# USB_and_CAN_Page_6.net
KiCad netlist of a schematic drawn in Altium Designer
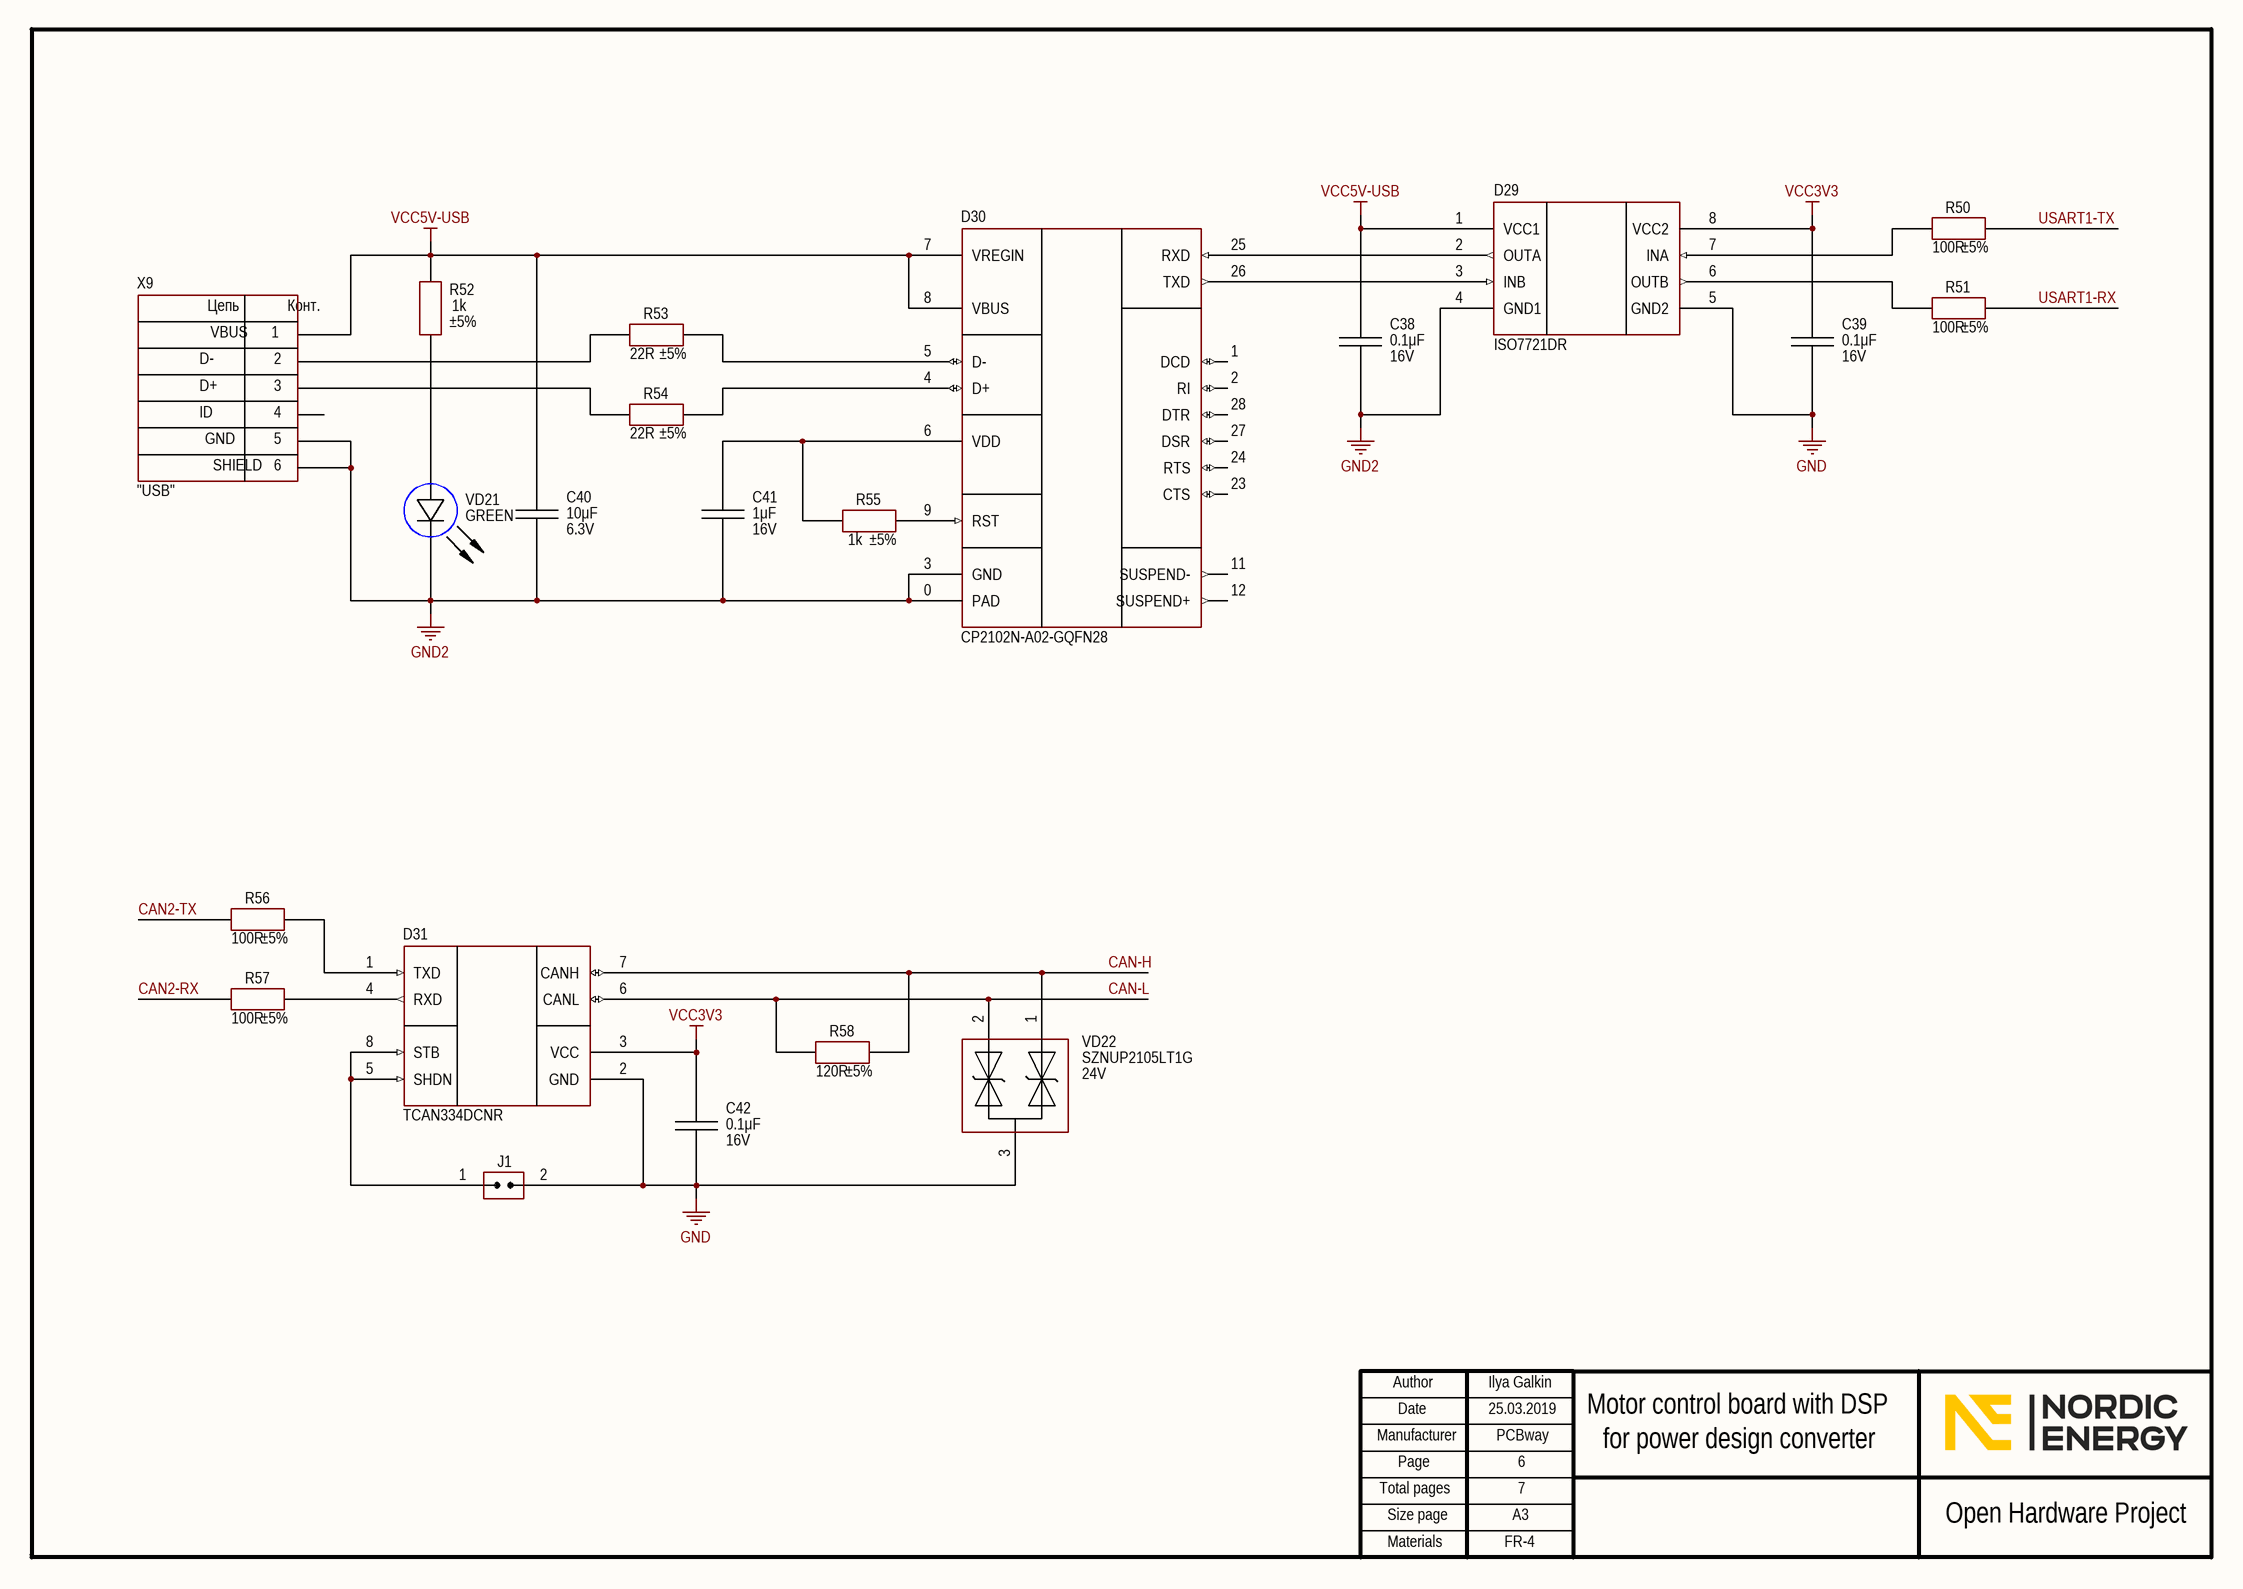
[diagram p0: USB and CAN. Page 6.SchDoc]

(export (version "E")
  (design (tool "Eeschema 10.0.6"))
  (components
    (comp (ref "C38")
      (value "0.1μF")
      (footprint "CAP: 0805")
      (fields
        (field (name "MANUFACTURER") "Yageo")
        (field (name "PARTNUMBER") "CC0805KRX7R7BB104")
        (field (name "VALUEMANUFACTURERPARTNUMBER") "Ceramic capacitor, 0.1μF, X7R, ±10%, 16V, 0805, -55...+125°C")
        (field (name "VOLTAGE") "16V")
      )
      (libsource (lib "Capacitor") (part "Ceramic_0805"))
    )
    (comp (ref "C39")
      (value "0.1μF")
      (footprint "CAP: 0805")
      (fields
        (field (name "MANUFACTURER") "Yageo")
        (field (name "PARTNUMBER") "CC0805KRX7R7BB104")
        (field (name "VALUEMANUFACTURERPARTNUMBER") "Ceramic capacitor, 0.1μF, X7R, ±10%, 16V, 0805, -55...+125°C")
        (field (name "VOLTAGE") "16V")
      )
      (libsource (lib "Capacitor") (part "Ceramic_0805"))
    )
    (comp (ref "C40")
      (value "10μF")
      (footprint "CAP: 0805")
      (fields
        (field (name "MANUFACTURER") "Samsung")
        (field (name "PARTNUMBER") "CL21B106KQQNNNE")
        (field (name "VALUEMANUFACTURERPARTNUMBER") "Ceramic capacitor, 10μF, X7R, ±10%, 6.3V, 0805, -55...+125°C")
        (field (name "VOLTAGE") "6.3V")
      )
      (libsource (lib "Capacitor") (part "Ceramic_0805"))
    )
    (comp (ref "C41")
      (value "1μF")
      (footprint "CAP: 0805")
      (fields
        (field (name "MANUFACTURER") "Yageo")
        (field (name "PARTNUMBER") "CC0805KKX7R7BB105")
        (field (name "VALUEMANUFACTURERPARTNUMBER") "Ceramic capacitor, 1μF, X7R, ±10%, 16V, 0805, -55...+125°C")
        (field (name "VOLTAGE") "16V")
      )
      (libsource (lib "Capacitor") (part "Ceramic_0805"))
    )
    (comp (ref "C42")
      (value "0.1μF")
      (footprint "CAP: 0805")
      (fields
        (field (name "MANUFACTURER") "Yageo")
        (field (name "PARTNUMBER") "CC0805KRX7R7BB104")
        (field (name "VALUEMANUFACTURERPARTNUMBER") "Ceramic capacitor, 0.1μF, X7R, ±10%, 16V, 0805, -55...+125°C")
        (field (name "VOLTAGE") "16V")
      )
      (libsource (lib "Capacitor") (part "Ceramic_0805"))
    )
    (comp (ref "D29")
      (value "~")
      (footprint "8-SOIC")
      (description "Digital isolator")
      (fields
        (field (name "MANUFACTURER") "Texas Instruments")
        (field (name "VALUEMANUFACTURERPARTNUMBER") "IC digital isolator, 100Mbps, 3000Vrms, 2.25...5.5V, -55...+125°C, 8-SOIC")
        (field (name "PARTNUMBER") "ISO7721DR")
      )
      (libsource (lib "IC. Interface") (part "ISO7721DR"))
    )
    (comp (ref "D30")
      (value "~")
      (footprint "28-QFN (5x5)")
      (description "USB-to-UART")
      (fields
        (field (name "MANUFACTURER") "Silicon Labs")
        (field (name "VALUEMANUFACTURERPARTNUMBER") "IC usb-to-uart bridge, USB2.0, 3...3.6V, -40...+85°C, 28-VFQFN")
        (field (name "PARTNUMBER") "CP2102N-A02-GQFN28")
      )
      (libsource (lib "IC. Interface") (part "CP2102N"))
    )
    (comp (ref "D31")
      (value "~")
      (footprint "SOT23-8")
      (description "CAN")
      (fields
        (field (name "MANUFACTURER") "Texas Instruments")
        (field (name "VALUEMANUFACTURERPARTNUMBER") "IC CAN transceiver, 1Mbps, Half-duplex, 3...3.6V, -40...+125°C, SOT23-8")
        (field (name "PARTNUMBER") "TCAN334DCNR")
      )
      (libsource (lib "IC. Interface") (part "TCAN334DCNR"))
    )
    (comp (ref "J1")
      (value "~")
      (footprint "CON: JUMPER x1")
      (libsource (lib "Connector") (part "Jumper_single"))
    )
    (comp (ref "R50")
      (value "100R")
      (footprint "RES: 0805")
      (fields
        (field (name "MANUFACTURER") "Yageo")
        (field (name "PARTNUMBER") "RC0805JR-07100RL")
        (field (name "VALUEMANUFACTURERPARTNUMBER") "Resistor film, 100R, ±5%, 0805, 0.125W, -55...+125°C")
        (field (name "TOLERANCE") "±5%")
      )
      (libsource (lib "Resistor") (part "Resistor_0805"))
    )
    (comp (ref "R51")
      (value "100R")
      (footprint "RES: 0805")
      (fields
        (field (name "MANUFACTURER") "Yageo")
        (field (name "PARTNUMBER") "RC0805JR-07100RL")
        (field (name "VALUEMANUFACTURERPARTNUMBER") "Resistor film, 100R, ±5%, 0805, 0.125W, -55...+125°C")
        (field (name "TOLERANCE") "±5%")
      )
      (libsource (lib "Resistor") (part "Resistor_0805"))
    )
    (comp (ref "R52")
      (value "1k")
      (footprint "RES: 0805")
      (fields
        (field (name "MANUFACTURER") "Yageo")
        (field (name "PARTNUMBER") "RC0805JR-071KL")
        (field (name "VALUEMANUFACTURERPARTNUMBER") "Resistor film, 1k, ±5%, 0805, 0.125W, -55...+125°C")
        (field (name "TOLERANCE") "±5%")
      )
      (libsource (lib "") (part "Resistor_0805_2"))
    )
    (comp (ref "R53")
      (value "22R")
      (footprint "RES: 0805")
      (fields
        (field (name "MANUFACTURER") "Yageo")
        (field (name "PARTNUMBER") "RC0805JR-0722RL")
        (field (name "VALUEMANUFACTURERPARTNUMBER") "Resistor film, 22R, ±5%, 0805, 0.125W, -55...+125°C")
        (field (name "TOLERANCE") "±5%")
      )
      (libsource (lib "Resistor") (part "Resistor_0805"))
    )
    (comp (ref "R54")
      (value "22R")
      (footprint "RES: 0805")
      (fields
        (field (name "MANUFACTURER") "Yageo")
        (field (name "PARTNUMBER") "RC0805JR-0722RL")
        (field (name "VALUEMANUFACTURERPARTNUMBER") "Resistor film, 22R, ±5%, 0805, 0.125W, -55...+125°C")
        (field (name "TOLERANCE") "±5%")
      )
      (libsource (lib "Resistor") (part "Resistor_0805"))
    )
    (comp (ref "R55")
      (value "1k")
      (footprint "RES: 0805")
      (fields
        (field (name "MANUFACTURER") "Yageo")
        (field (name "PARTNUMBER") "RC0805JR-071KL")
        (field (name "VALUEMANUFACTURERPARTNUMBER") "Resistor film, 1k, ±5%, 0805, 0.125W, -55...+125°C")
        (field (name "TOLERANCE") "±5%")
      )
      (libsource (lib "") (part "Resistor_0805_1"))
    )
    (comp (ref "R56")
      (value "100R")
      (footprint "RES: 0805")
      (fields
        (field (name "MANUFACTURER") "Yageo")
        (field (name "PARTNUMBER") "RC0805JR-07100RL")
        (field (name "VALUEMANUFACTURERPARTNUMBER") "Resistor film, 100R, ±5%, 0805, 0.125W, -55...+125°C")
        (field (name "TOLERANCE") "±5%")
      )
      (libsource (lib "Resistor") (part "Resistor_0805"))
    )
    (comp (ref "R57")
      (value "100R")
      (footprint "RES: 0805")
      (fields
        (field (name "MANUFACTURER") "Yageo")
        (field (name "PARTNUMBER") "RC0805JR-07100RL")
        (field (name "VALUEMANUFACTURERPARTNUMBER") "Resistor film, 100R, ±5%, 0805, 0.125W, -55...+125°C")
        (field (name "TOLERANCE") "±5%")
      )
      (libsource (lib "Resistor") (part "Resistor_0805"))
    )
    (comp (ref "R58")
      (value "120R")
      (footprint "RES: 0805")
      (fields
        (field (name "MANUFACTURER") "Yageo")
        (field (name "PARTNUMBER") "RC0805JR-07120RL")
        (field (name "VALUEMANUFACTURERPARTNUMBER") "Resistor film, 120R, ±5%, 0805, 0.125W, -55...+125°C")
        (field (name "TOLERANCE") "±5%")
      )
      (libsource (lib "Resistor") (part "Resistor_0805"))
    )
    (comp (ref "VD21")
      (value "~")
      (footprint "LED: 0603G")
      (fields
        (field (name "MANUFACTURER") "Wurth")
        (field (name "VALUEMANUFACTURERPARTNUMBER") "LED, 20mA, 2V, 0805, -55...+150°C")
        (field (name "PARTNUMBER") "150080VS75000")
        (field (name "COLOR") "GREEN")
      )
      (libsource (lib "Diode") (part "LED_single"))
    )
    (comp (ref "VD22")
      (value "~")
      (footprint "SOT23")
      (fields
        (field (name "MANUFACTURER") "ON Semiconductor")
        (field (name "VALUEMANUFACTURERPARTNUMBER") "Zener diode, 24V, 350W peak, 30pF, 17Ohm, SOT-23, -55...+150°C")
        (field (name "VOLTAGE") "24V")
        (field (name "PARTNUMBER") "SZNUP2105LT1G")
      )
      (libsource (lib "Diode") (part "TVS_array"))
    )
    (comp (ref "X9")
      (value "~")
      (footprint "CON: USB micro-A (ZX62-B-5PA)")
      (fields
        (field (name "MANUFACTURER") "Hirose Electric")
        (field (name "VALUEMANUFACTURERPARTNUMBER") "USB micro B")
        (field (name "PARTNUMBER") "ZX62-B-5PA")
        (field (name "COMMENTTEXT") "\"USB\"")
      )
      (libsource (lib "Connector") (part "Connector_USB_micro_B"))
    )
  )
  (nets
    (net (code "1") (name "/CAN-H") (class "Default")
      (node (ref "D31") (pin "7") (pinfunction "CANH_7") (pintype "bidirectional"))
      (node (ref "R58") (pin "2") (pinfunction "2_2") (pintype "passive"))
      (node (ref "VD22") (pin "1") (pintype "passive"))
    )
    (net (code "2") (name "/CAN-L") (class "Default")
      (node (ref "D31") (pin "6") (pinfunction "CANL_6") (pintype "bidirectional"))
      (node (ref "R58") (pin "1") (pinfunction "1_1") (pintype "passive"))
      (node (ref "VD22") (pin "2") (pintype "passive"))
    )
    (net (code "3") (name "/CAN2-RX") (class "Default")
      (node (ref "R57") (pin "1") (pinfunction "1_1") (pintype "passive"))
    )
    (net (code "4") (name "/CAN2-TX") (class "Default")
      (node (ref "R56") (pin "1") (pinfunction "1_1") (pintype "passive"))
    )
    (net (code "5") (name "/USART1-RX") (class "Default")
      (node (ref "R51") (pin "2") (pinfunction "2_2") (pintype "passive"))
    )
    (net (code "6") (name "/USART1-TX") (class "Default")
      (node (ref "R50") (pin "2") (pinfunction "2_2") (pintype "passive"))
    )
    (net (code "7") (name "GND") (class "Default")
      (node (ref "C39") (pin "1") (pinfunction "1_1") (pintype "power_in"))
      (node (ref "C42") (pin "1") (pinfunction "1_1") (pintype "power_in"))
      (node (ref "D29") (pin "5") (pinfunction "GND2_5") (pintype "passive"))
      (node (ref "D31") (pin "2") (pinfunction "GND_2") (pintype "passive"))
      (node (ref "J1") (pin "2") (pinfunction "IN_2") (pintype "passive"))
      (node (ref "VD22") (pin "3") (pintype "passive"))
    )
    (net (code "8") (name "GND2") (class "Default")
      (node (ref "C38") (pin "1") (pinfunction "1_1") (pintype "power_in"))
      (node (ref "C40") (pin "1") (pinfunction "1_1") (pintype "power_in"))
      (node (ref "C41") (pin "1") (pinfunction "1_1") (pintype "power_in"))
      (node (ref "D29") (pin "4") (pinfunction "GND1_4") (pintype "passive"))
      (node (ref "D30") (pin "0") (pinfunction "PAD_0") (pintype "passive"))
      (node (ref "D30") (pin "3") (pinfunction "GND_3") (pintype "passive"))
      (node (ref "VD21") (pin "2") (pinfunction "C_2") (pintype "passive"))
      (node (ref "X9") (pin "0") (pinfunction "0_0") (pintype "passive"))
      (node (ref "X9") (pin "5") (pinfunction "5_5") (pintype "passive"))
    )
    (net (code "9") (name "Net-(D29-INA)") (class "Default")
      (node (ref "D29") (pin "7") (pinfunction "INA_7") (pintype "input"))
      (node (ref "R50") (pin "1") (pinfunction "1_1") (pintype "passive"))
    )
    (net (code "10") (name "Net-(D29-INB)") (class "Default")
      (node (ref "D29") (pin "3") (pinfunction "INB_3") (pintype "input"))
      (node (ref "D30") (pin "26") (pinfunction "TXD_26") (pintype "output"))
    )
    (net (code "11") (name "Net-(D29-OUTA)") (class "Default")
      (node (ref "D29") (pin "2") (pinfunction "OUTA_2") (pintype "output"))
      (node (ref "D30") (pin "25") (pinfunction "RXD_25") (pintype "input"))
    )
    (net (code "12") (name "Net-(D29-OUTB)") (class "Default")
      (node (ref "D29") (pin "6") (pinfunction "OUTB_6") (pintype "output"))
      (node (ref "R51") (pin "1") (pinfunction "1_1") (pintype "passive"))
    )
    (net (code "13") (name "Net-(D30-D+)") (class "Default")
      (node (ref "D30") (pin "4") (pinfunction "D+_4") (pintype "bidirectional"))
      (node (ref "R54") (pin "2") (pinfunction "2_2") (pintype "passive"))
    )
    (net (code "14") (name "Net-(D30-D-)") (class "Default")
      (node (ref "D30") (pin "5") (pinfunction "D-_5") (pintype "bidirectional"))
      (node (ref "R53") (pin "2") (pinfunction "2_2") (pintype "passive"))
    )
    (net (code "15") (name "Net-(D30-RST)") (class "Default")
      (node (ref "D30") (pin "9") (pinfunction "RST_9") (pintype "input"))
      (node (ref "R55") (pin "1") (pinfunction "1_1") (pintype "passive"))
    )
    (net (code "16") (name "Net-(D30-VDD)") (class "Default")
      (node (ref "C41") (pin "2") (pinfunction "2_2") (pintype "power_in"))
      (node (ref "D30") (pin "6") (pinfunction "VDD_6") (pintype "passive"))
      (node (ref "R55") (pin "2") (pinfunction "2_2") (pintype "passive"))
    )
    (net (code "17") (name "Net-(D31-RXD)") (class "Default")
      (node (ref "D31") (pin "4") (pinfunction "RXD_4") (pintype "output"))
      (node (ref "R57") (pin "2") (pinfunction "2_2") (pintype "passive"))
    )
    (net (code "18") (name "Net-(D31-SHDN)") (class "Default")
      (node (ref "D31") (pin "5") (pinfunction "SHDN_5") (pintype "input"))
      (node (ref "D31") (pin "8") (pinfunction "STB_8") (pintype "input"))
      (node (ref "J1") (pin "1") (pinfunction "IN_1") (pintype "passive"))
    )
    (net (code "19") (name "Net-(D31-TXD)") (class "Default")
      (node (ref "D31") (pin "1") (pinfunction "TXD_1") (pintype "input"))
      (node (ref "R56") (pin "2") (pinfunction "2_2") (pintype "passive"))
    )
    (net (code "20") (name "Net-(R53-Pad1)") (class "Default")
      (node (ref "R53") (pin "1") (pinfunction "1_1") (pintype "passive"))
      (node (ref "X9") (pin "2") (pinfunction "2_2") (pintype "passive"))
    )
    (net (code "21") (name "Net-(R54-Pad1)") (class "Default")
      (node (ref "R54") (pin "1") (pinfunction "1_1") (pintype "passive"))
      (node (ref "X9") (pin "3") (pinfunction "3_3") (pintype "passive"))
    )
    (net (code "22") (name "Net-(VD21-A)") (class "Default")
      (node (ref "R52") (pin "1") (pinfunction "1_1") (pintype "passive"))
      (node (ref "VD21") (pin "1") (pinfunction "A_1") (pintype "passive"))
    )
    (net (code "23") (name "VCC3V3") (class "Default")
      (node (ref "C39") (pin "2") (pinfunction "2_2") (pintype "power_in"))
      (node (ref "C42") (pin "2") (pinfunction "2_2") (pintype "power_in"))
      (node (ref "D29") (pin "8") (pinfunction "VCC2_8") (pintype "passive"))
      (node (ref "D31") (pin "3") (pinfunction "VCC_3") (pintype "passive"))
    )
    (net (code "24") (name "VCC5V-USB") (class "Default")
      (node (ref "C38") (pin "2") (pinfunction "2_2") (pintype "power_in"))
      (node (ref "C40") (pin "2") (pinfunction "2_2") (pintype "power_in"))
      (node (ref "D29") (pin "1") (pinfunction "VCC1_1") (pintype "passive"))
      (node (ref "D30") (pin "7") (pinfunction "VREGIN_7") (pintype "passive"))
      (node (ref "D30") (pin "8") (pinfunction "VBUS_8") (pintype "passive"))
      (node (ref "R52") (pin "2") (pinfunction "2_2") (pintype "passive"))
      (node (ref "X9") (pin "1") (pintype "passive"))
    )
    (net (code "25") (name "unconnected-(D30-CTS-Pad23)") (class "Default")
      (node (ref "D30") (pin "23") (pinfunction "CTS_23") (pintype "bidirectional"))
    )
    (net (code "26") (name "unconnected-(D30-DCD-Pad1)") (class "Default")
      (node (ref "D30") (pin "1") (pinfunction "DCD_1") (pintype "bidirectional"))
    )
    (net (code "27") (name "unconnected-(D30-DSR-Pad27)") (class "Default")
      (node (ref "D30") (pin "27") (pinfunction "DSR_27") (pintype "bidirectional"))
    )
    (net (code "28") (name "unconnected-(D30-DTR-Pad28)") (class "Default")
      (node (ref "D30") (pin "28") (pinfunction "DTR_28") (pintype "bidirectional"))
    )
    (net (code "29") (name "unconnected-(D30-RI-Pad2)") (class "Default")
      (node (ref "D30") (pin "2") (pinfunction "RI_2") (pintype "bidirectional"))
    )
    (net (code "30") (name "unconnected-(D30-RTS-Pad24)") (class "Default")
      (node (ref "D30") (pin "24") (pinfunction "RTS_24") (pintype "bidirectional"))
    )
    (net (code "31") (name "unconnected-(D30-SUSPEND+-Pad12)") (class "Default")
      (node (ref "D30") (pin "12") (pinfunction "SUSPEND+_12") (pintype "output"))
    )
    (net (code "32") (name "unconnected-(D30-SUSPEND--Pad11)") (class "Default")
      (node (ref "D30") (pin "11") (pinfunction "SUSPEND-_11") (pintype "output"))
    )
    (net (code "33") (name "unconnected-(X9-Pad4)") (class "Default")
      (node (ref "X9") (pin "4") (pinfunction "4_4") (pintype "passive"))
    )
  )
)
